# YarnControl_motor_v1_0.net
KiCad netlist of a schematic drawn in Altium Designer
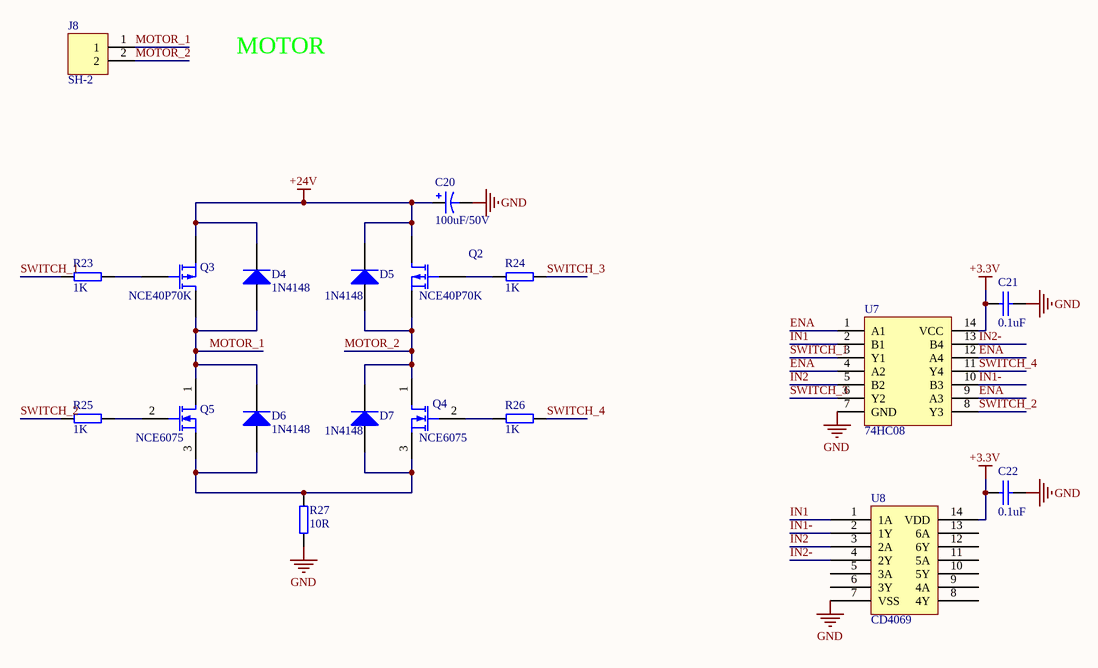
[diagram p0: YarnControl_motor_v1.0.SchDoc]

(export (version "E")
  (design (tool "Eeschema 10.0.6"))
  (components
    (comp (ref "C20")
      (value "100uF/50V")
      (footprint "CAP-5mm")
      (description "Polarized Capacitor (Radial)")
      (fields (field (name "PUBLISHER") "Altium Limited"))
      (libsource (lib "Miscellaneous Devices") (part "Cap Pol1"))
    )
    (comp (ref "C21")
      (value "0.1uF")
      (footprint "0805")
      (description "电容")
      (libsource (lib "Component") (part "CAP"))
    )
    (comp (ref "C22")
      (value "0.1uF")
      (footprint "0805")
      (description "电容")
      (libsource (lib "Component") (part "CAP"))
    )
    (comp (ref "D4")
      (value "1N4148")
      (footprint "DIDODE_LL-34")
      (description "Default Diode")
      (fields (field (name "PUBLISHER") "Altium Limited"))
      (libsource (lib "Miscellaneous Devices") (part "Diode"))
    )
    (comp (ref "D5")
      (value "1N4148")
      (footprint "DIDODE_LL-34")
      (description "Default Diode")
      (fields (field (name "PUBLISHER") "Altium Limited"))
      (libsource (lib "Miscellaneous Devices") (part "Diode"))
    )
    (comp (ref "D6")
      (value "1N4148")
      (footprint "DIDODE_LL-34")
      (description "Default Diode")
      (fields (field (name "PUBLISHER") "Altium Limited"))
      (libsource (lib "Miscellaneous Devices") (part "Diode"))
    )
    (comp (ref "D7")
      (value "1N4148")
      (footprint "DIDODE_LL-34")
      (description "Default Diode")
      (fields (field (name "PUBLISHER") "Altium Limited"))
      (libsource (lib "Miscellaneous Devices") (part "Diode"))
    )
    (comp (ref "J8") (value "SH-2") (footprint "CH3.96-2P") (libsource (lib "Connector") (part "SH-2")))
    (comp (ref "Q2")
      (value "NCE40P70K")
      (footprint "TO-252")
      (description "P-Channel MOSFET")
      (fields (field (name "PUBLISHER") "Altium Limited"))
      (libsource (lib "Miscellaneous Devices") (part "MOSFET-P"))
    )
    (comp (ref "Q3")
      (value "NCE40P70K")
      (footprint "TO-252")
      (description "P-Channel MOSFET")
      (fields (field (name "PUBLISHER") "Altium Limited"))
      (libsource (lib "Miscellaneous Devices") (part "MOSFET-P"))
    )
    (comp (ref "Q4")
      (value "NCE6075")
      (footprint "TO-252")
      (description "N-Channel MOSFET")
      (fields (field (name "PUBLISHER") "Altium Limited"))
      (libsource (lib "Miscellaneous Devices") (part "MOSFET-N"))
    )
    (comp (ref "Q5")
      (value "NCE6075")
      (footprint "TO-252")
      (description "N-Channel MOSFET")
      (fields (field (name "PUBLISHER") "Altium Limited"))
      (libsource (lib "Miscellaneous Devices") (part "MOSFET-N"))
    )
    (comp (ref "R23")
      (value "1K")
      (footprint "0805")
      (description "电阻")
      (libsource (lib "Component") (part "RES"))
    )
    (comp (ref "R24")
      (value "1K")
      (footprint "0805")
      (description "电阻")
      (libsource (lib "Component") (part "RES"))
    )
    (comp (ref "R25")
      (value "1K")
      (footprint "0805")
      (description "电阻")
      (libsource (lib "Component") (part "RES"))
    )
    (comp (ref "R26")
      (value "1K")
      (footprint "0805")
      (description "电阻")
      (libsource (lib "Component") (part "RES"))
    )
    (comp (ref "R27")
      (value "10R")
      (footprint "1210")
      (description "电阻")
      (libsource (lib "Component") (part "RES"))
    )
    (comp (ref "U7") (value "74HC08") (footprint "SO-14") (libsource (lib "Chip") (part "74HC08")))
    (comp (ref "U8") (value "CD4069") (footprint "SO-14") (libsource (lib "Chip") (part "CD4069")))
  )
  (nets
    (net (code "1") (name "+3.3V") (class "Default")
      (node (ref "C21") (pin "1") (pinfunction "1_1") (pintype "passive"))
      (node (ref "C22") (pin "1") (pinfunction "1_1") (pintype "passive"))
      (node (ref "U7") (pin "14") (pinfunction "VCC_14") (pintype "passive"))
      (node (ref "U8") (pin "14") (pinfunction "VDD_14") (pintype "passive"))
    )
    (net (code "2") (name "+24V") (class "Default")
      (node (ref "C20") (pin "1") (pinfunction "1_1") (pintype "passive"))
      (node (ref "D4") (pin "2") (pinfunction "K_2") (pintype "passive"))
      (node (ref "D5") (pin "2") (pinfunction "K_2") (pintype "passive"))
      (node (ref "Q2") (pin "1") (pinfunction "D_1") (pintype "passive"))
      (node (ref "Q3") (pin "3") (pinfunction "S_3") (pintype "passive"))
    )
    (net (code "3") (name "/ENA") (class "Default")
      (node (ref "U7") (pin "1") (pinfunction "A1_1") (pintype "passive"))
      (node (ref "U7") (pin "12") (pinfunction "A4_12") (pintype "passive"))
      (node (ref "U7") (pin "4") (pinfunction "A2_4") (pintype "passive"))
      (node (ref "U7") (pin "9") (pinfunction "A3_9") (pintype "passive"))
    )
    (net (code "4") (name "/IN1") (class "Default")
      (node (ref "U7") (pin "2") (pinfunction "B1_2") (pintype "passive"))
      (node (ref "U8") (pin "1") (pinfunction "1A_1") (pintype "passive"))
    )
    (net (code "5") (name "/IN1-") (class "Default")
      (node (ref "U7") (pin "10") (pinfunction "B3_10") (pintype "passive"))
      (node (ref "U8") (pin "2") (pinfunction "1Y_2") (pintype "passive"))
    )
    (net (code "6") (name "/IN2") (class "Default")
      (node (ref "U7") (pin "5") (pinfunction "B2_5") (pintype "passive"))
      (node (ref "U8") (pin "3") (pinfunction "2A_3") (pintype "passive"))
    )
    (net (code "7") (name "/IN2-") (class "Default")
      (node (ref "U7") (pin "13") (pinfunction "B4_13") (pintype "passive"))
      (node (ref "U8") (pin "4") (pinfunction "2Y_4") (pintype "passive"))
    )
    (net (code "8") (name "/MOTOR_1") (class "Default")
      (node (ref "D4") (pin "1") (pinfunction "A_1") (pintype "passive"))
      (node (ref "D6") (pin "2") (pinfunction "K_2") (pintype "passive"))
      (node (ref "J8") (pin "1") (pinfunction "1_1") (pintype "passive"))
      (node (ref "Q3") (pin "1") (pinfunction "D_1") (pintype "passive"))
      (node (ref "Q5") (pin "1") (pinfunction "D_1") (pintype "passive"))
    )
    (net (code "9") (name "/MOTOR_2") (class "Default")
      (node (ref "D5") (pin "1") (pinfunction "A_1") (pintype "passive"))
      (node (ref "D7") (pin "2") (pinfunction "K_2") (pintype "passive"))
      (node (ref "J8") (pin "2") (pinfunction "2_2") (pintype "passive"))
      (node (ref "Q2") (pin "3") (pinfunction "S_3") (pintype "passive"))
      (node (ref "Q4") (pin "1") (pinfunction "D_1") (pintype "passive"))
    )
    (net (code "10") (name "/SWITCH_1") (class "Default")
      (node (ref "R23") (pin "1") (pinfunction "1_1") (pintype "passive"))
      (node (ref "U7") (pin "3") (pinfunction "Y1_3") (pintype "passive"))
    )
    (net (code "11") (name "/SWITCH_2") (class "Default")
      (node (ref "R25") (pin "1") (pinfunction "1_1") (pintype "passive"))
      (node (ref "U7") (pin "8") (pinfunction "Y3_8") (pintype "passive"))
    )
    (net (code "12") (name "/SWITCH_3") (class "Default")
      (node (ref "R24") (pin "2") (pinfunction "2_2") (pintype "passive"))
      (node (ref "U7") (pin "6") (pinfunction "Y2_6") (pintype "passive"))
    )
    (net (code "13") (name "/SWITCH_4") (class "Default")
      (node (ref "R26") (pin "2") (pinfunction "2_2") (pintype "passive"))
      (node (ref "U7") (pin "11") (pinfunction "Y4_11") (pintype "passive"))
    )
    (net (code "14") (name "GND") (class "Default")
      (node (ref "C20") (pin "2") (pinfunction "2_2") (pintype "passive"))
      (node (ref "C21") (pin "2") (pinfunction "2_2") (pintype "passive"))
      (node (ref "C22") (pin "2") (pinfunction "2_2") (pintype "passive"))
      (node (ref "R27") (pin "1") (pinfunction "1_1") (pintype "passive"))
      (node (ref "U7") (pin "7") (pinfunction "GND_7") (pintype "passive"))
      (node (ref "U8") (pin "7") (pinfunction "VSS_7") (pintype "passive"))
    )
    (net (code "15") (name "Net-(D6-A)") (class "Default")
      (node (ref "D6") (pin "1") (pinfunction "A_1") (pintype "passive"))
      (node (ref "D7") (pin "1") (pinfunction "A_1") (pintype "passive"))
      (node (ref "Q4") (pin "3") (pinfunction "S_3") (pintype "passive"))
      (node (ref "Q5") (pin "3") (pinfunction "S_3") (pintype "passive"))
      (node (ref "R27") (pin "2") (pinfunction "2_2") (pintype "passive"))
    )
    (net (code "16") (name "Net-(Q2-G)") (class "Default")
      (node (ref "Q2") (pin "2") (pinfunction "G_2") (pintype "passive"))
      (node (ref "R24") (pin "1") (pinfunction "1_1") (pintype "passive"))
    )
    (net (code "17") (name "Net-(Q3-G)") (class "Default")
      (node (ref "Q3") (pin "2") (pinfunction "G_2") (pintype "passive"))
      (node (ref "R23") (pin "2") (pinfunction "2_2") (pintype "passive"))
    )
    (net (code "18") (name "Net-(Q4-G)") (class "Default")
      (node (ref "Q4") (pin "2") (pinfunction "G_2") (pintype "passive"))
      (node (ref "R26") (pin "1") (pinfunction "1_1") (pintype "passive"))
    )
    (net (code "19") (name "Net-(Q5-G)") (class "Default")
      (node (ref "Q5") (pin "2") (pinfunction "G_2") (pintype "passive"))
      (node (ref "R25") (pin "2") (pinfunction "2_2") (pintype "passive"))
    )
    (net (code "20") (name "unconnected-(U8-3A-Pad5)") (class "Default")
      (node (ref "U8") (pin "5") (pinfunction "3A_5") (pintype "passive"))
    )
    (net (code "21") (name "unconnected-(U8-3Y-Pad6)") (class "Default")
      (node (ref "U8") (pin "6") (pinfunction "3Y_6") (pintype "passive"))
    )
    (net (code "22") (name "unconnected-(U8-4A-Pad9)") (class "Default")
      (node (ref "U8") (pin "9") (pinfunction "4A_9") (pintype "passive"))
    )
    (net (code "23") (name "unconnected-(U8-4Y-Pad8)") (class "Default")
      (node (ref "U8") (pin "8") (pinfunction "4Y_8") (pintype "passive"))
    )
    (net (code "24") (name "unconnected-(U8-5A-Pad11)") (class "Default")
      (node (ref "U8") (pin "11") (pinfunction "5A_11") (pintype "passive"))
    )
    (net (code "25") (name "unconnected-(U8-5Y-Pad10)") (class "Default")
      (node (ref "U8") (pin "10") (pinfunction "5Y_10") (pintype "passive"))
    )
    (net (code "26") (name "unconnected-(U8-6A-Pad13)") (class "Default")
      (node (ref "U8") (pin "13") (pinfunction "6A_13") (pintype "passive"))
    )
    (net (code "27") (name "unconnected-(U8-6Y-Pad12)") (class "Default")
      (node (ref "U8") (pin "12") (pinfunction "6Y_12") (pintype "passive"))
    )
  )
)
